# rfm.net
KiCad netlist of a schematic drawn in Altium Designer
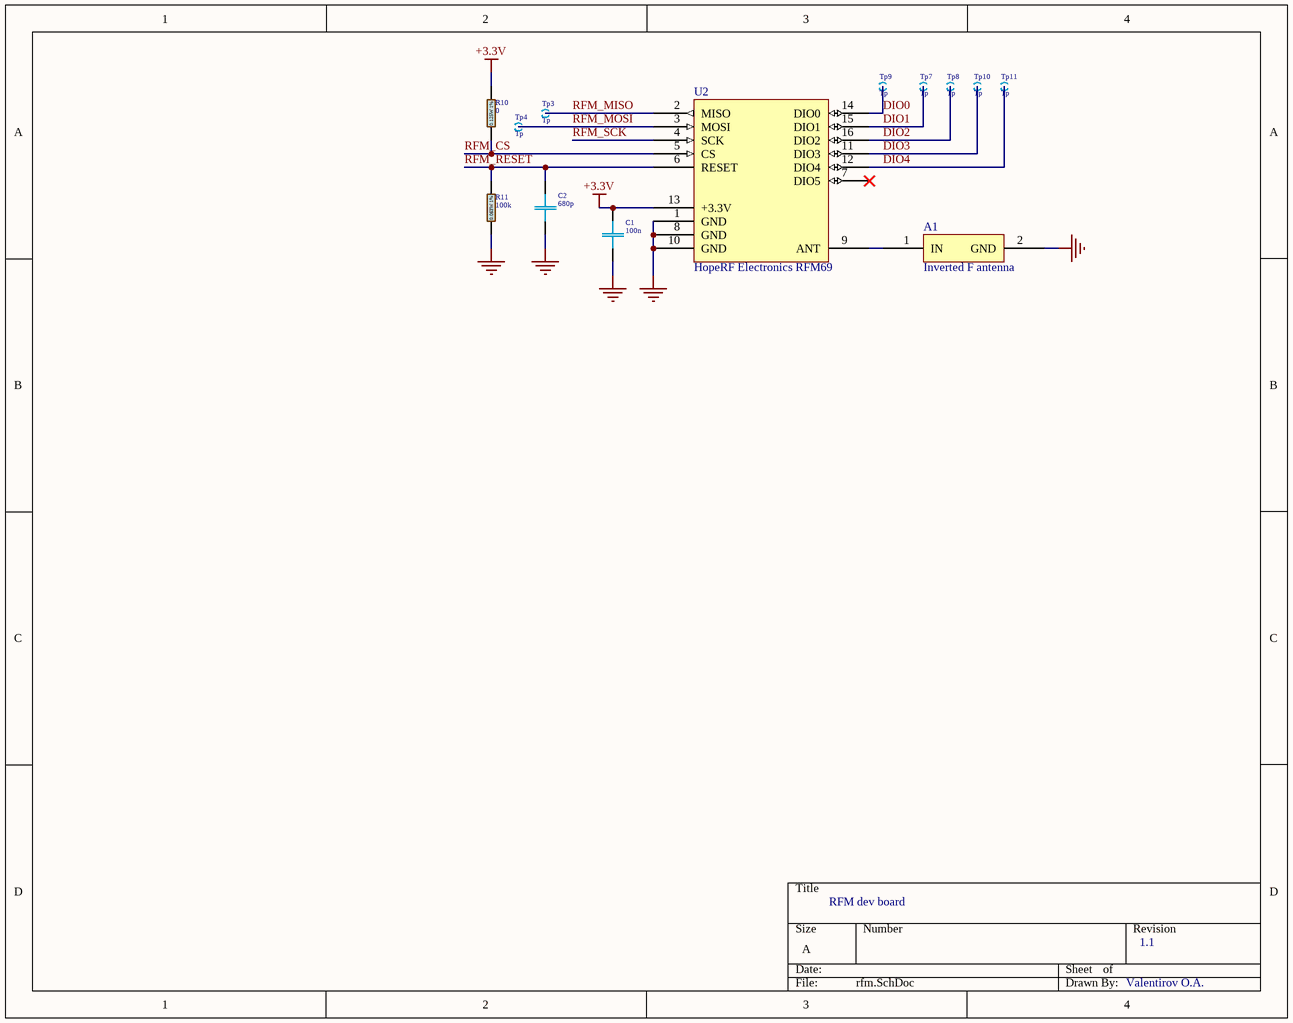
[diagram p0: rfm.SchDoc]

(export (version "E")
  (design (tool "Eeschema 10.0.6"))
  (components
    (comp (ref "A1")
      (value "Inverted F antenna")
      (footprint "Invertef_F-footprint")
      (libsource (lib "radio") (part "inverted_F"))
    )
    (comp (ref "C1")
      (value "100n")
      (footprint "C 0402(1005)x0.5")
      (description "SMD 0402     16V X5R 10%")
      (fields (field (name "MANUFACTURER") "Samsung") (field (name "PUBLISHER") "Hefest"))
      (libsource (lib "SMD Passive") (part "C 0402    16V X5R - 0*"))
    )
    (comp (ref "C2")
      (value "680p")
      (footprint "C 0402(1005)x0.5")
      (description "SMD 0402     16V X5R 10%")
      (fields (field (name "MANUFACTURER") "Samsung") (field (name "PUBLISHER") "Hefest"))
      (libsource (lib "SMD Passive") (part "C 0402    16V X5R - 0*"))
    )
    (comp (ref "R10")
      (value "0")
      (footprint "R 0805(2012)-1%")
      (description "SMD 0805 0.125W 1% 150V")
      (fields
        (field (name "MANUFACTURER") "YAGEO")
        (field (name "POWER") "0.125W")
        (field (name "PUBLISHER") "Hefest")
      )
      (libsource (lib "SMD Passive") (part "R 0805-1%"))
    )
    (comp (ref "R11")
      (value "100k")
      (footprint "R 0402(1005)-1%")
      (description "SMD 0402 0.063W 1%   50V")
      (fields
        (field (name "MANUFACTURER") "YAGEO")
        (field (name "POWER") "0.0625W")
        (field (name "PUBLISHER") "Hefest")
      )
      (libsource (lib "SMD Passive") (part "R 0402-1%"))
    )
    (comp (ref "Tp3")
      (value "Tp")
      (footprint "Tp-0.5")
      (description "TestPoint")
      (fields (field (name "PUBLISHER") "Hefest"))
      (libsource (lib "SMD Passive") (part "Tp"))
    )
    (comp (ref "Tp4")
      (value "Tp")
      (footprint "Tp-0.5")
      (description "TestPoint")
      (fields (field (name "PUBLISHER") "Hefest"))
      (libsource (lib "SMD Passive") (part "Tp"))
    )
    (comp (ref "Tp7")
      (value "Tp")
      (footprint "Tp-0.5")
      (description "TestPoint")
      (fields (field (name "PUBLISHER") "Hefest"))
      (libsource (lib "SMD Passive") (part "Tp"))
    )
    (comp (ref "Tp8")
      (value "Tp")
      (footprint "Tp-0.5")
      (description "TestPoint")
      (fields (field (name "PUBLISHER") "Hefest"))
      (libsource (lib "SMD Passive") (part "Tp"))
    )
    (comp (ref "Tp9")
      (value "Tp")
      (footprint "Tp-0.5")
      (description "TestPoint")
      (fields (field (name "PUBLISHER") "Hefest"))
      (libsource (lib "SMD Passive") (part "Tp"))
    )
    (comp (ref "Tp10")
      (value "Tp")
      (footprint "Tp-0.5")
      (description "TestPoint")
      (fields (field (name "PUBLISHER") "Hefest"))
      (libsource (lib "SMD Passive") (part "Tp"))
    )
    (comp (ref "Tp11")
      (value "Tp")
      (footprint "Tp-0.5")
      (description "TestPoint")
      (fields (field (name "PUBLISHER") "Hefest"))
      (libsource (lib "SMD Passive") (part "Tp"))
    )
    (comp (ref "U2")
      (value "HopeRF Electronics RFM69")
      (footprint "CAC-200P1600X1600-16N")
      (libsource (lib "radio") (part "RFM69"))
    )
  )
  (nets
    (net (code "1") (name "+3.3V") (class "Default")
      (node (ref "C1") (pin "1") (pinfunction "1_1") (pintype "passive"))
      (node (ref "R10") (pin "2") (pinfunction "2_2") (pintype "passive"))
      (node (ref "U2") (pin "13") (pinfunction "+3.3V_13") (pintype "passive"))
    )
    (net (code "2") (name "/DIO0") (class "Default")
      (node (ref "Tp9") (pin "1") (pinfunction "1_1") (pintype "passive"))
      (node (ref "U2") (pin "14") (pinfunction "DIO0_14") (pintype "bidirectional"))
    )
    (net (code "3") (name "/DIO1") (class "Default")
      (node (ref "Tp7") (pin "1") (pinfunction "1_1") (pintype "passive"))
      (node (ref "U2") (pin "15") (pinfunction "DIO1_15") (pintype "bidirectional"))
    )
    (net (code "4") (name "/DIO2") (class "Default")
      (node (ref "Tp8") (pin "1") (pinfunction "1_1") (pintype "passive"))
      (node (ref "U2") (pin "16") (pinfunction "DIO2_16") (pintype "bidirectional"))
    )
    (net (code "5") (name "/DIO3") (class "Default")
      (node (ref "Tp10") (pin "1") (pinfunction "1_1") (pintype "passive"))
      (node (ref "U2") (pin "11") (pinfunction "DIO3_11") (pintype "bidirectional"))
    )
    (net (code "6") (name "/DIO4") (class "Default")
      (node (ref "Tp11") (pin "1") (pinfunction "1_1") (pintype "passive"))
      (node (ref "U2") (pin "12") (pinfunction "DIO4_12") (pintype "bidirectional"))
    )
    (net (code "7") (name "/RFM_CS") (class "Default")
      (node (ref "R10") (pin "1") (pinfunction "1_1") (pintype "passive"))
      (node (ref "U2") (pin "5") (pinfunction "CS_5") (pintype "input"))
    )
    (net (code "8") (name "/RFM_MISO") (class "Default")
      (node (ref "Tp3") (pin "1") (pinfunction "1_1") (pintype "passive"))
      (node (ref "U2") (pin "2") (pinfunction "MISO_2") (pintype "output"))
    )
    (net (code "9") (name "/RFM_MOSI") (class "Default")
      (node (ref "Tp4") (pin "1") (pinfunction "1_1") (pintype "passive"))
      (node (ref "U2") (pin "3") (pinfunction "MOSI_3") (pintype "input"))
    )
    (net (code "10") (name "/RFM_RESET") (class "Default")
      (node (ref "C2") (pin "1") (pinfunction "1_1") (pintype "passive"))
      (node (ref "R11") (pin "2") (pinfunction "2_2") (pintype "passive"))
      (node (ref "U2") (pin "6") (pinfunction "RESET_6") (pintype "passive"))
    )
    (net (code "11") (name "/RFM_SCK") (class "Default")
      (node (ref "U2") (pin "4") (pinfunction "SCK_4") (pintype "input"))
    )
    (net (code "12") (name "GND") (class "Default")
      (node (ref "A1") (pin "2") (pinfunction "GND_2") (pintype "passive"))
      (node (ref "C1") (pin "2") (pinfunction "2_2") (pintype "passive"))
      (node (ref "C2") (pin "2") (pinfunction "2_2") (pintype "passive"))
      (node (ref "R11") (pin "1") (pinfunction "1_1") (pintype "passive"))
      (node (ref "U2") (pin "1") (pinfunction "GND_1") (pintype "passive"))
      (node (ref "U2") (pin "10") (pinfunction "GND_10") (pintype "passive"))
      (node (ref "U2") (pin "8") (pinfunction "GND_8") (pintype "passive"))
    )
    (net (code "13") (name "Net-(A1-IN)") (class "Default")
      (node (ref "A1") (pin "1") (pinfunction "IN_1") (pintype "passive"))
      (node (ref "U2") (pin "9") (pinfunction "ANT_9") (pintype "passive"))
    )
    (net (code "14") (name "unconnected-(U2-DIO5-Pad7)") (class "Default")
      (node (ref "U2") (pin "7") (pinfunction "DIO5_7") (pintype "bidirectional+no_connect"))
    )
  )
)
